# M5_Display_GPIO.net
KiCad netlist of a schematic drawn in Altium Designer
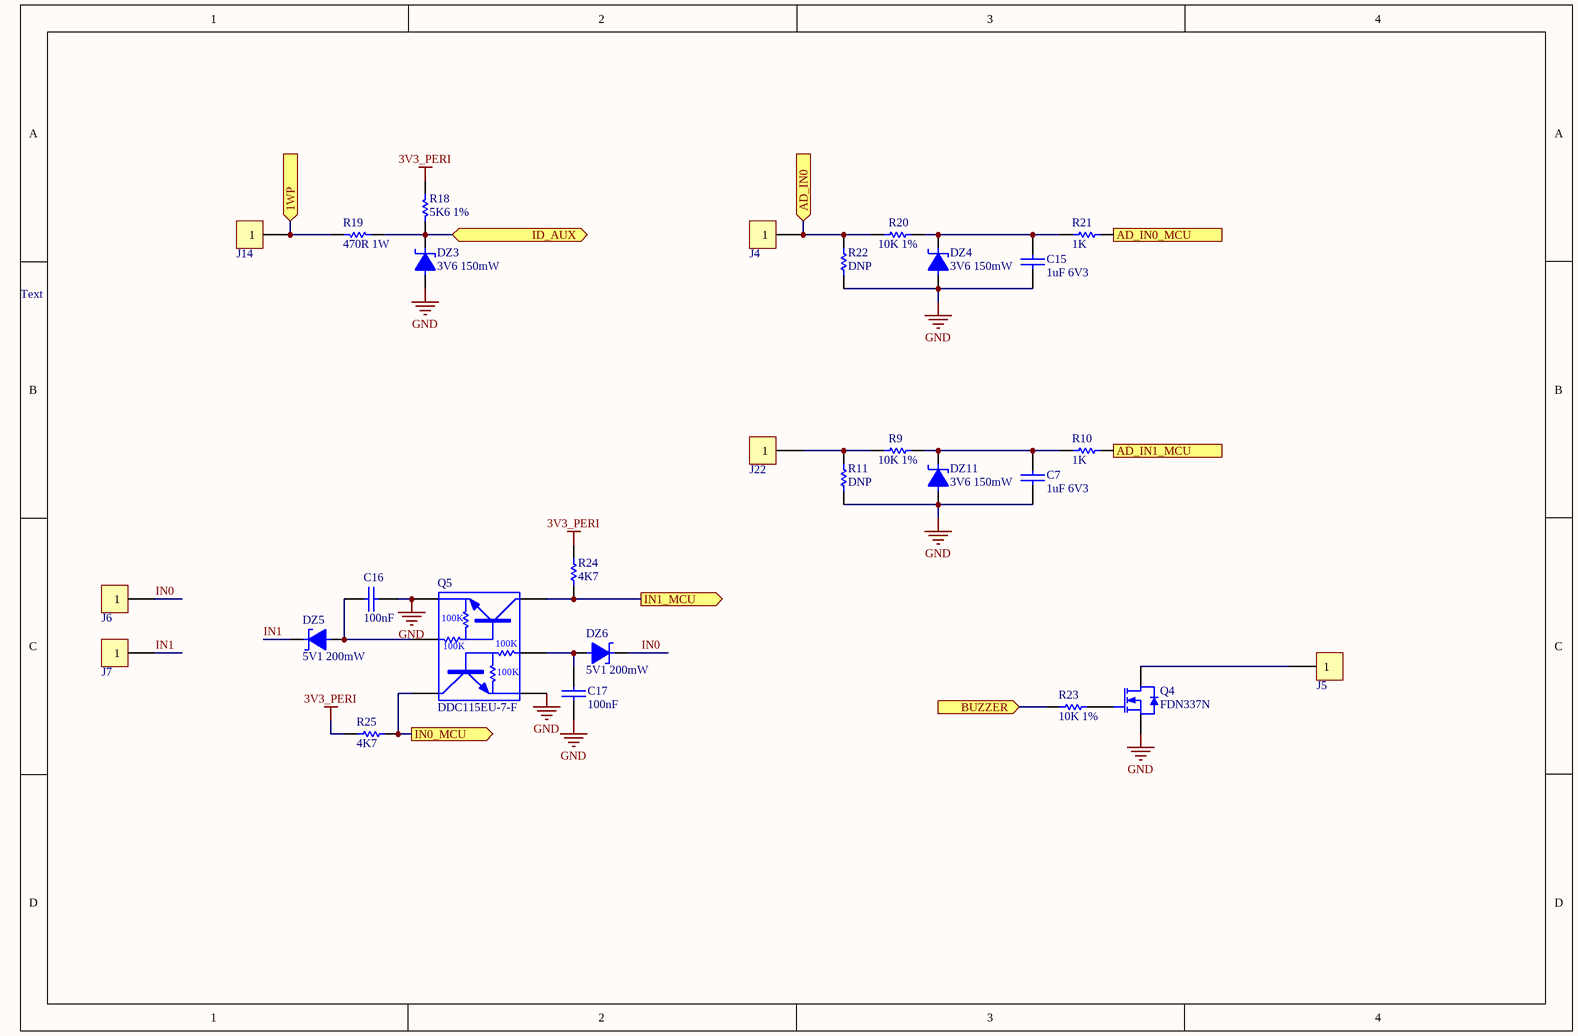
[diagram p0: M5_Display_GPIO.SchDoc]

(export (version "E")
  (design (tool "Eeschema 10.0.6"))
  (components
    (comp (ref "C7")
      (value "1uF 6V3")
      (footprint "0402")
      (description "CAP0402 1uF 6V3 X7R")
      (fields
        (field (name "PART NUMBER") "CAP0402_1uF_6V3_X7R")
        (field (name "MANUFACTURER") "Samsung Electro-Mechanics")
      )
      (libsource (lib "gl_LIB") (part "CAP"))
    )
    (comp (ref "C15")
      (value "1uF 6V3")
      (footprint "0402")
      (description "CAP0402 1uF 6V3 X7R")
      (fields
        (field (name "PART NUMBER") "CAP0402_1uF_6V3_X7R")
        (field (name "MANUFACTURER") "Samsung Electro-Mechanics")
      )
      (libsource (lib "gl_LIB") (part "CAP"))
    )
    (comp (ref "C16")
      (value "100nF")
      (footprint "0402")
      (description "CAP0402 100nF 50V X7R")
      (fields
        (field (name "PART NUMBER") "CAP0402_100nF_50V_X7R")
        (field (name "MANUFACTURER") "TDK Corporation")
      )
      (libsource (lib "gl_LIB") (part "CAP"))
    )
    (comp (ref "C17")
      (value "100nF")
      (footprint "0402")
      (description "CAP0402 100nF 50V X7R")
      (fields
        (field (name "PART NUMBER") "CAP0402_100nF_50V_X7R")
        (field (name "MANUFACTURER") "TDK Corporation")
      )
      (libsource (lib "gl_LIB") (part "CAP"))
    )
    (comp (ref "DZ3")
      (value "3V6 150mW")
      (footprint "SOD523")
      (description "DIODE ZENER 3.6V 150MW SSMINI2 SOD523")
      (fields
        (field (name "PART NUMBER") "DIO_ZEN_3V6_SOD523")
        (field (name "MANUFACTURER") "Panasonic Electronic Components")
      )
      (libsource (lib "gl_LIB") (part "DIODO ZENER"))
    )
    (comp (ref "DZ4")
      (value "3V6 150mW")
      (footprint "SOD523")
      (description "DIODE ZENER 3.6V 150MW SSMINI2 SOD523")
      (fields
        (field (name "PART NUMBER") "DIO_ZEN_3V6_SOD523")
        (field (name "MANUFACTURER") "Panasonic Electronic Components")
      )
      (libsource (lib "gl_LIB") (part "DIODO ZENER"))
    )
    (comp (ref "DZ5")
      (value "5V1 200mW")
      (footprint "SOD523")
      (description "DIODE ZENER 5.1V 200MW SOD523F")
      (fields (field (name "PART NUMBER") "DIO_ZEN_5V1_200mW_SOD523") (field (name "MANUFACTURER") "MM5Z5V1"))
      (libsource (lib "gl_LIB") (part "DIODO ZENER"))
    )
    (comp (ref "DZ6")
      (value "5V1 200mW")
      (footprint "SOD523")
      (description "DIODE ZENER 5.1V 200MW SOD523F")
      (fields (field (name "PART NUMBER") "DIO_ZEN_5V1_200mW_SOD523") (field (name "MANUFACTURER") "MM5Z5V1"))
      (libsource (lib "gl_LIB") (part "DIODO ZENER"))
    )
    (comp (ref "DZ11")
      (value "3V6 150mW")
      (footprint "SOD523")
      (description "DIODE ZENER 3.6V 150MW SSMINI2 SOD523")
      (fields
        (field (name "PART NUMBER") "DIO_ZEN_3V6_SOD523")
        (field (name "MANUFACTURER") "Panasonic Electronic Components")
      )
      (libsource (lib "gl_LIB") (part "DIODO ZENER"))
    )
    (comp (ref "J4")
      (value "PIN CABLE")
      (footprint "PIN_CABLE")
      (description "PIN PARA SOLDAR CABLE 1MM")
      (fields (field (name "PART NUMBER") "PIN_1_CABLE_1mm"))
      (libsource (lib "gl_LIB") (part "CON1_TRAMPA"))
    )
    (comp (ref "J5")
      (value "PIN CABLE")
      (footprint "PIN_CABLE")
      (description "PIN PARA SOLDAR CABLE 1MM")
      (fields (field (name "PART NUMBER") "PIN_1_CABLE_1mm"))
      (libsource (lib "") (part "CON1_TRAMPA_1"))
    )
    (comp (ref "J6")
      (value "PIN CABLE")
      (footprint "PIN_CABLE")
      (description "PIN PARA SOLDAR CABLE 1MM")
      (fields (field (name "PART NUMBER") "PIN_1_CABLE_1mm"))
      (libsource (lib "gl_LIB") (part "CON1_TRAMPA"))
    )
    (comp (ref "J7")
      (value "PIN CABLE")
      (footprint "PIN_CABLE")
      (description "PIN PARA SOLDAR CABLE 1MM")
      (fields (field (name "PART NUMBER") "PIN_1_CABLE_1mm"))
      (libsource (lib "gl_LIB") (part "CON1_TRAMPA"))
    )
    (comp (ref "J14")
      (value "PIN CABLE")
      (footprint "PIN_CABLE")
      (description "PIN PARA SOLDAR CABLE 1MM")
      (fields (field (name "PART NUMBER") "PIN_1_CABLE_1mm"))
      (libsource (lib "gl_LIB") (part "CON1_TRAMPA"))
    )
    (comp (ref "J22")
      (value "PIN CABLE")
      (footprint "PIN_CABLE")
      (description "PIN PARA SOLDAR CABLE 1MM")
      (fields (field (name "PART NUMBER") "PIN_1_CABLE_1mm"))
      (libsource (lib "gl_LIB") (part "CON1_TRAMPA"))
    )
    (comp (ref "Q4")
      (value "FDN337N")
      (footprint "SOT23")
      (description "MOSFET N-CH 30V 2.2A SSOT3")
      (fields (field (name "PART NUMBER") "FDN337N_SOT23"))
      (libsource (lib "gl_LIB") (part "MOSFET N"))
    )
    (comp (ref "Q5")
      (value "DDC115EU-7-F")
      (footprint "SOT363")
      (description "TRANS BRT NPN DUAL 50V SOT-363 Rb=100K Rbe=100K")
      (fields
        (field (name "PART NUMBER") "DDC115EU-7-F_SOT363")
        (field (name "MANUFACTURER") "Diodes Incorporated")
      )
      (libsource (lib "gl_LIB") (part "DDC115EU-7-F"))
    )
    (comp (ref "R9")
      (value "10K 1%")
      (footprint "0402")
      (description "RES0402 10K 1%")
      (fields (field (name "PART NUMBER") "RES0402_10K_1%"))
      (libsource (lib "gl_LIB") (part "RES"))
    )
    (comp (ref "R10")
      (value "1K")
      (footprint "0402")
      (description "RES0402 1K 5%")
      (fields (field (name "PART NUMBER") "RES0402_1K_5%"))
      (libsource (lib "gl_LIB") (part "RES"))
    )
    (comp (ref "R11")
      (value "DNP")
      (footprint "0805")
      (description "RES0805 DNP")
      (fields (field (name "PART NUMBER") "RES0805_DNP"))
      (libsource (lib "gl_LIB") (part "RES_DNP"))
    )
    (comp (ref "R18")
      (value "5K6 1%")
      (footprint "0402")
      (description "RES0402 5K6 1%")
      (fields
        (field (name "PART NUMBER") "RES0402_5K6_1%")
        (field (name "MANUFACTURER") "Stackpole Electronics Inc")
      )
      (libsource (lib "gl_LIB") (part "RES"))
    )
    (comp (ref "R19")
      (value "470R 1W")
      (footprint "2010")
      (description "RES2010 470R 1W 5%")
      (fields
        (field (name "PART NUMBER") "RES2010_470R_1W_5%")
        (field (name "MANUFACTURER") "Stackpole Electronics Inc")
      )
      (libsource (lib "gl_LIB") (part "RES"))
    )
    (comp (ref "R20")
      (value "10K 1%")
      (footprint "0402")
      (description "RES0402 10K 1%")
      (fields (field (name "PART NUMBER") "RES0402_10K_1%"))
      (libsource (lib "gl_LIB") (part "RES"))
    )
    (comp (ref "R21")
      (value "1K")
      (footprint "0402")
      (description "RES0402 1K 5%")
      (fields (field (name "PART NUMBER") "RES0402_1K_5%"))
      (libsource (lib "gl_LIB") (part "RES"))
    )
    (comp (ref "R22")
      (value "DNP")
      (footprint "0805")
      (description "RES0805 DNP")
      (fields (field (name "PART NUMBER") "RES0805_DNP"))
      (libsource (lib "gl_LIB") (part "RES_DNP"))
    )
    (comp (ref "R23")
      (value "10K 1%")
      (footprint "0402")
      (description "RES0402 10K 1%")
      (fields (field (name "PART NUMBER") "RES0402_10K_1%"))
      (libsource (lib "gl_LIB") (part "RES"))
    )
    (comp (ref "R24")
      (value "4K7")
      (footprint "0402")
      (description "RES0402 4K7 5%")
      (fields
        (field (name "PART NUMBER") "RES0402_4K7_5%")
        (field (name "MANUFACTURER") "Stackpole Electronics Inc")
      )
      (libsource (lib "gl_LIB") (part "RES"))
    )
    (comp (ref "R25")
      (value "4K7")
      (footprint "0402")
      (description "RES0402 4K7 5%")
      (fields
        (field (name "PART NUMBER") "RES0402_4K7_5%")
        (field (name "MANUFACTURER") "Stackpole Electronics Inc")
      )
      (libsource (lib "gl_LIB") (part "RES"))
    )
  )
  (nets
    (net (code "1") (name "/1WP") (class "Default")
      (node (ref "J14") (pin "1") (pinfunction "1_1") (pintype "passive"))
      (node (ref "R19") (pin "2") (pinfunction "2_2") (pintype "passive"))
    )
    (net (code "2") (name "/AD_IN0") (class "Default")
      (node (ref "J4") (pin "1") (pinfunction "1_1") (pintype "passive"))
      (node (ref "R20") (pin "1") (pinfunction "1_1") (pintype "passive"))
      (node (ref "R22") (pin "2") (pinfunction "2_2") (pintype "passive"))
    )
    (net (code "3") (name "/AD_IN0_MCU") (class "Default")
      (node (ref "R21") (pin "1") (pinfunction "1_1") (pintype "passive"))
    )
    (net (code "4") (name "/AD_IN1_MCU") (class "Default")
      (node (ref "R10") (pin "1") (pinfunction "1_1") (pintype "passive"))
    )
    (net (code "5") (name "/BUZZER") (class "Default")
      (node (ref "R23") (pin "2") (pinfunction "2_2") (pintype "passive"))
    )
    (net (code "6") (name "/ID_AUX") (class "Default")
      (node (ref "DZ3") (pin "2") (pinfunction "2_2") (pintype "passive"))
      (node (ref "R18") (pin "1") (pinfunction "1_1") (pintype "passive"))
      (node (ref "R19") (pin "1") (pinfunction "1_1") (pintype "passive"))
    )
    (net (code "7") (name "/IN0") (class "Default")
      (node (ref "DZ6") (pin "2") (pinfunction "2_2") (pintype "passive"))
      (node (ref "J6") (pin "1") (pinfunction "1_1") (pintype "passive"))
    )
    (net (code "8") (name "/IN0_MCU") (class "Default")
      (node (ref "Q5") (pin "3") (pinfunction "CQ2_3") (pintype "passive"))
      (node (ref "R25") (pin "2") (pinfunction "2_2") (pintype "passive"))
    )
    (net (code "9") (name "/IN1") (class "Default")
      (node (ref "DZ5") (pin "2") (pinfunction "2_2") (pintype "passive"))
      (node (ref "J7") (pin "1") (pinfunction "1_1") (pintype "passive"))
    )
    (net (code "10") (name "/IN1_MCU") (class "Default")
      (node (ref "Q5") (pin "6") (pinfunction "CQ1_6") (pintype "passive"))
      (node (ref "R24") (pin "2") (pinfunction "2_2") (pintype "passive"))
    )
    (net (code "11") (name "3V3_PERI") (class "Default")
      (node (ref "R18") (pin "2") (pinfunction "2_2") (pintype "passive"))
      (node (ref "R24") (pin "1") (pinfunction "1_1") (pintype "passive"))
      (node (ref "R25") (pin "1") (pinfunction "1_1") (pintype "passive"))
    )
    (net (code "12") (name "GND") (class "Default")
      (node (ref "C15") (pin "2") (pinfunction "2_2") (pintype "passive"))
      (node (ref "C16") (pin "2") (pinfunction "2_2") (pintype "passive"))
      (node (ref "C17") (pin "2") (pinfunction "2_2") (pintype "passive"))
      (node (ref "C7") (pin "2") (pinfunction "2_2") (pintype "passive"))
      (node (ref "DZ11") (pin "1") (pinfunction "1_1") (pintype "passive"))
      (node (ref "DZ3") (pin "1") (pinfunction "1_1") (pintype "passive"))
      (node (ref "DZ4") (pin "1") (pinfunction "1_1") (pintype "passive"))
      (node (ref "Q4") (pin "3") (pinfunction "S_3") (pintype "passive"))
      (node (ref "Q5") (pin "1") (pinfunction "EQ1_1") (pintype "passive"))
      (node (ref "Q5") (pin "4") (pinfunction "EQ2_4") (pintype "passive"))
      (node (ref "R11") (pin "1") (pinfunction "1_1") (pintype "passive"))
      (node (ref "R22") (pin "1") (pinfunction "1_1") (pintype "passive"))
    )
    (net (code "13") (name "Net-(C7-Pad1)") (class "Default")
      (node (ref "C7") (pin "1") (pinfunction "1_1") (pintype "passive"))
      (node (ref "DZ11") (pin "2") (pinfunction "2_2") (pintype "passive"))
      (node (ref "R10") (pin "2") (pinfunction "2_2") (pintype "passive"))
      (node (ref "R9") (pin "2") (pinfunction "2_2") (pintype "passive"))
    )
    (net (code "14") (name "Net-(C15-Pad1)") (class "Default")
      (node (ref "C15") (pin "1") (pinfunction "1_1") (pintype "passive"))
      (node (ref "DZ4") (pin "2") (pinfunction "2_2") (pintype "passive"))
      (node (ref "R20") (pin "2") (pinfunction "2_2") (pintype "passive"))
      (node (ref "R21") (pin "2") (pinfunction "2_2") (pintype "passive"))
    )
    (net (code "15") (name "Net-(J22-Pad1)") (class "Default")
      (node (ref "J22") (pin "1") (pinfunction "1_1") (pintype "passive"))
      (node (ref "R11") (pin "2") (pinfunction "2_2") (pintype "passive"))
      (node (ref "R9") (pin "1") (pinfunction "1_1") (pintype "passive"))
    )
    (net (code "16") (name "Net-(Q4-D)") (class "Default")
      (node (ref "J5") (pin "1") (pinfunction "1_1") (pintype "passive"))
      (node (ref "Q4") (pin "2") (pinfunction "D_2") (pintype "passive"))
    )
    (net (code "17") (name "Net-(Q4-G)") (class "Default")
      (node (ref "Q4") (pin "1") (pinfunction "G_1") (pintype "passive"))
      (node (ref "R23") (pin "1") (pinfunction "1_1") (pintype "passive"))
    )
    (net (code "18") (name "Net-(Q5-BQ1)") (class "Default")
      (node (ref "C16") (pin "1") (pinfunction "1_1") (pintype "passive"))
      (node (ref "DZ5") (pin "1") (pinfunction "1_1") (pintype "passive"))
      (node (ref "Q5") (pin "2") (pinfunction "BQ1_2") (pintype "passive"))
    )
    (net (code "19") (name "Net-(Q5-BQ2)") (class "Default")
      (node (ref "C17") (pin "1") (pinfunction "1_1") (pintype "passive"))
      (node (ref "DZ6") (pin "1") (pinfunction "1_1") (pintype "passive"))
      (node (ref "Q5") (pin "5") (pinfunction "BQ2_5") (pintype "passive"))
    )
  )
)
